# gyro.net
KiCad netlist of a schematic drawn in EAGLE
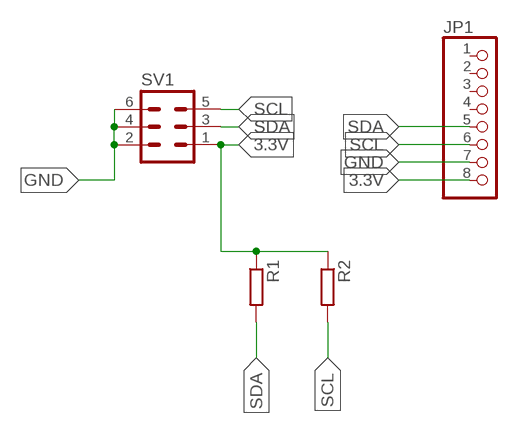
[diagram p0: schematic, sheet 1]

(export (version "E")
  (design (tool "Eeschema 10.0.6"))
  (components
    (comp (ref "JP1")
      (value "PINHD-1X8")
      (footprint "eagle-import:1X08")
      (libsource (lib "eagle-import") (part "PINHD-1X8"))
    )
    (comp (ref "R1")
      (value "R-EU_0309/12")
      (footprint "eagle-import:0309_12")
      (libsource (lib "eagle-import") (part "R-EU_0309/12"))
    )
    (comp (ref "R2")
      (value "R-EU_0309/12")
      (footprint "eagle-import:0309_12")
      (libsource (lib "eagle-import") (part "R-EU_0309/12"))
    )
    (comp (ref "SV1")
      (value "ML6")
      (footprint "eagle-import:ML6")
      (libsource (lib "eagle-import") (part "ML6"))
    )
  )
  (nets
    (net (code "1") (name "3.3V") (class "Default")
      (node (ref "JP1") (pin "8") (pinfunction "8_8") (pintype "passive"))
      (node (ref "R1") (pin "1") (pinfunction "1_1") (pintype "passive"))
      (node (ref "R2") (pin "1") (pinfunction "1_1") (pintype "passive"))
      (node (ref "SV1") (pin "1") (pinfunction "1_1") (pintype "passive"))
    )
    (net (code "2") (name "GND") (class "Default")
      (node (ref "JP1") (pin "7") (pinfunction "7_7") (pintype "passive"))
      (node (ref "SV1") (pin "2") (pinfunction "2_2") (pintype "passive"))
      (node (ref "SV1") (pin "4") (pinfunction "4_4") (pintype "passive"))
      (node (ref "SV1") (pin "6") (pinfunction "6_6") (pintype "passive"))
    )
    (net (code "3") (name "SCL") (class "Default")
      (node (ref "JP1") (pin "6") (pinfunction "6_6") (pintype "passive"))
      (node (ref "R2") (pin "2") (pinfunction "2_2") (pintype "passive"))
      (node (ref "SV1") (pin "5") (pinfunction "5_5") (pintype "passive"))
    )
    (net (code "4") (name "SDA") (class "Default")
      (node (ref "JP1") (pin "5") (pinfunction "5_5") (pintype "passive"))
      (node (ref "R1") (pin "2") (pinfunction "2_2") (pintype "passive"))
      (node (ref "SV1") (pin "3") (pinfunction "3_3") (pintype "passive"))
    )
    (net (code "5") (name "unconnected-(JP1-Pad1)") (class "Default")
      (node (ref "JP1") (pin "1") (pinfunction "1_1") (pintype "passive"))
    )
    (net (code "6") (name "unconnected-(JP1-Pad2)") (class "Default")
      (node (ref "JP1") (pin "2") (pinfunction "2_2") (pintype "passive"))
    )
    (net (code "7") (name "unconnected-(JP1-Pad3)") (class "Default")
      (node (ref "JP1") (pin "3") (pinfunction "3_3") (pintype "passive"))
    )
    (net (code "8") (name "unconnected-(JP1-Pad4)") (class "Default")
      (node (ref "JP1") (pin "4") (pinfunction "4_4") (pintype "passive"))
    )
  )
)
